# Proto_buttons.net
KiCad netlist of a schematic drawn in Altium Designer
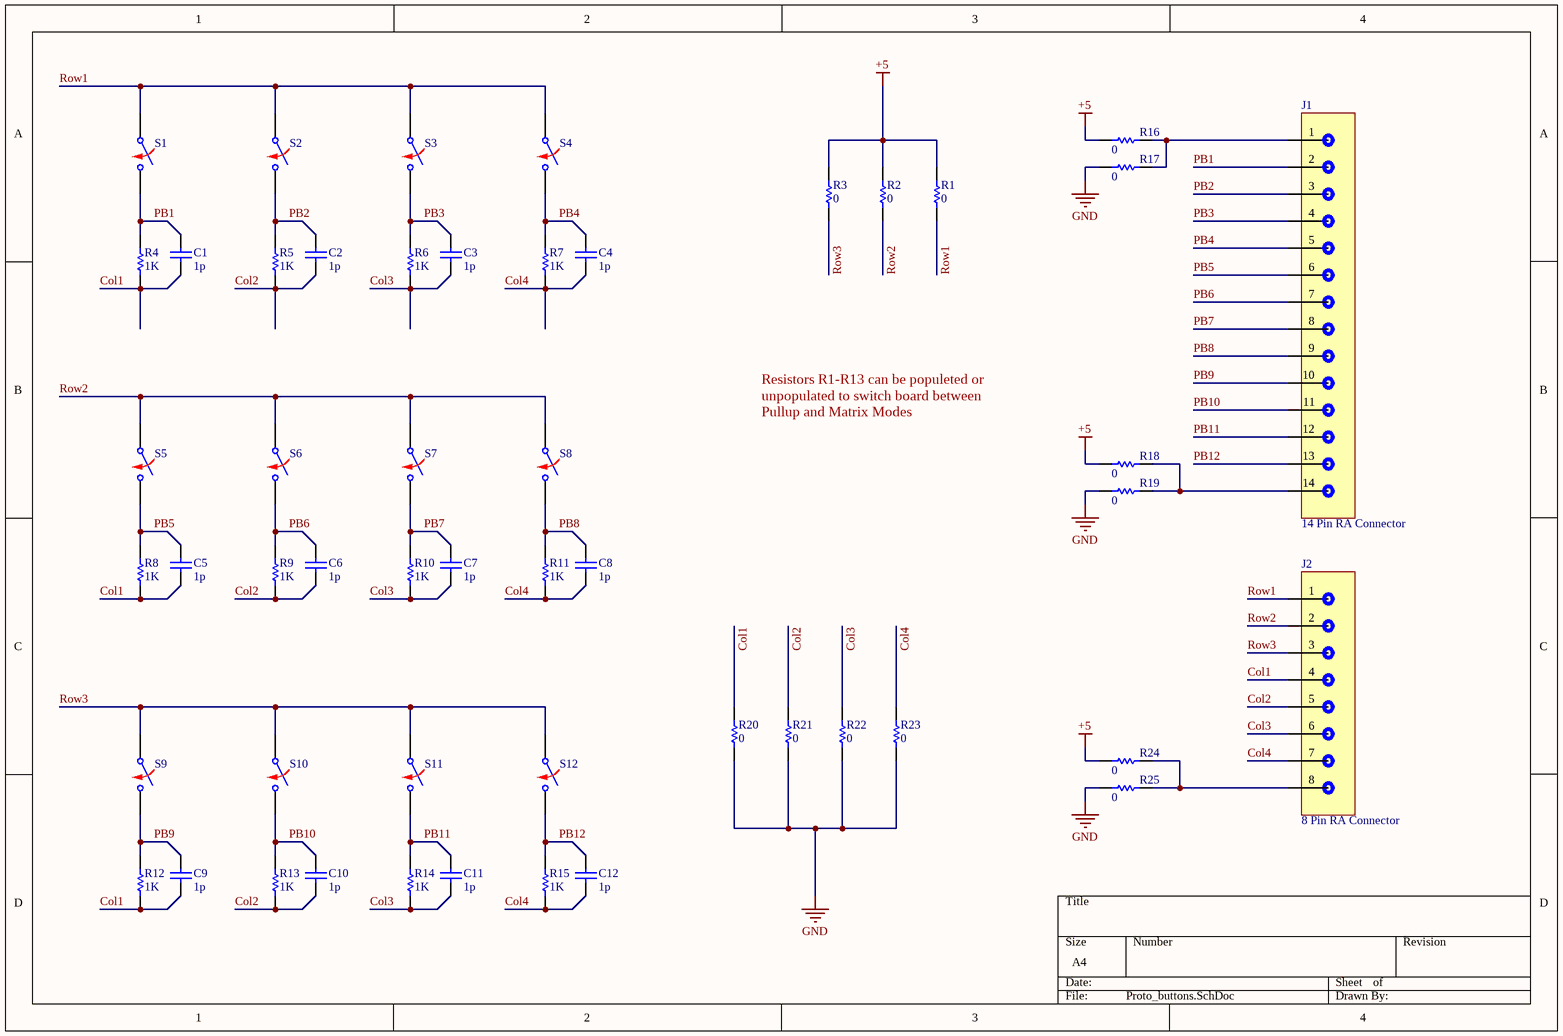
[diagram p0: Proto_buttons.SchDoc]

(export (version "E")
  (design (tool "Eeschema 10.0.6"))
  (components
    (comp (ref "C1")
      (value "1p")
      (footprint "TDK_CC0603_N")
      (description "Capacitor")
      (libsource (lib "Simulation Generic Components") (part "Capacitor"))
    )
    (comp (ref "C2")
      (value "1p")
      (footprint "TDK_CC0603_N")
      (description "Capacitor")
      (libsource (lib "Simulation Generic Components") (part "Capacitor"))
    )
    (comp (ref "C3")
      (value "1p")
      (footprint "TDK_CC0603_N")
      (description "Capacitor")
      (libsource (lib "Simulation Generic Components") (part "Capacitor"))
    )
    (comp (ref "C4")
      (value "1p")
      (footprint "TDK_CC0603_N")
      (description "Capacitor")
      (libsource (lib "Simulation Generic Components") (part "Capacitor"))
    )
    (comp (ref "C5")
      (value "1p")
      (footprint "TDK_CC0603_N")
      (description "Capacitor")
      (libsource (lib "Simulation Generic Components") (part "Capacitor"))
    )
    (comp (ref "C6")
      (value "1p")
      (footprint "TDK_CC0603_N")
      (description "Capacitor")
      (libsource (lib "Simulation Generic Components") (part "Capacitor"))
    )
    (comp (ref "C7")
      (value "1p")
      (footprint "TDK_CC0603_N")
      (description "Capacitor")
      (libsource (lib "Simulation Generic Components") (part "Capacitor"))
    )
    (comp (ref "C8")
      (value "1p")
      (footprint "TDK_CC0603_N")
      (description "Capacitor")
      (libsource (lib "Simulation Generic Components") (part "Capacitor"))
    )
    (comp (ref "C9")
      (value "1p")
      (footprint "TDK_CC0603_N")
      (description "Capacitor")
      (libsource (lib "Simulation Generic Components") (part "Capacitor"))
    )
    (comp (ref "C10")
      (value "1p")
      (footprint "TDK_CC0603_N")
      (description "Capacitor")
      (libsource (lib "Simulation Generic Components") (part "Capacitor"))
    )
    (comp (ref "C11")
      (value "1p")
      (footprint "TDK_CC0603_N")
      (description "Capacitor")
      (libsource (lib "Simulation Generic Components") (part "Capacitor"))
    )
    (comp (ref "C12")
      (value "1p")
      (footprint "TDK_CC0603_N")
      (description "Capacitor")
      (libsource (lib "Simulation Generic Components") (part "Capacitor"))
    )
    (comp (ref "J1")
      (value "14 Pin RA Connector")
      (footprint "14pin-Edge Connector")
      (libsource (lib "BW_Symbols") (part "14 Pin RA Connector"))
    )
    (comp (ref "J2")
      (value "8 Pin RA Connector")
      (footprint "8pin-Edge Connector")
      (libsource (lib "BW_Symbols") (part "8 Pin RA Connector"))
    )
    (comp (ref "R1")
      (value "0")
      (footprint "Yageo_0603")
      (description "Resistor")
      (libsource (lib "Simulation Generic Components") (part "Resistor"))
    )
    (comp (ref "R2")
      (value "0")
      (footprint "Yageo_0603")
      (description "Resistor")
      (libsource (lib "Simulation Generic Components") (part "Resistor"))
    )
    (comp (ref "R3")
      (value "0")
      (footprint "Yageo_0603")
      (description "Resistor")
      (libsource (lib "Simulation Generic Components") (part "Resistor"))
    )
    (comp (ref "R4")
      (value "1K")
      (footprint "Yageo_0603")
      (description "Resistor")
      (libsource (lib "Simulation Generic Components") (part "Resistor"))
    )
    (comp (ref "R5")
      (value "1K")
      (footprint "Yageo_0603")
      (description "Resistor")
      (libsource (lib "Simulation Generic Components") (part "Resistor"))
    )
    (comp (ref "R6")
      (value "1K")
      (footprint "Yageo_0603")
      (description "Resistor")
      (libsource (lib "Simulation Generic Components") (part "Resistor"))
    )
    (comp (ref "R7")
      (value "1K")
      (footprint "Yageo_0603")
      (description "Resistor")
      (libsource (lib "Simulation Generic Components") (part "Resistor"))
    )
    (comp (ref "R8")
      (value "1K")
      (footprint "Yageo_0603")
      (description "Resistor")
      (libsource (lib "Simulation Generic Components") (part "Resistor"))
    )
    (comp (ref "R9")
      (value "1K")
      (footprint "Yageo_0603")
      (description "Resistor")
      (libsource (lib "Simulation Generic Components") (part "Resistor"))
    )
    (comp (ref "R10")
      (value "1K")
      (footprint "Yageo_0603")
      (description "Resistor")
      (libsource (lib "Simulation Generic Components") (part "Resistor"))
    )
    (comp (ref "R11")
      (value "1K")
      (footprint "Yageo_0603")
      (description "Resistor")
      (libsource (lib "Simulation Generic Components") (part "Resistor"))
    )
    (comp (ref "R12")
      (value "1K")
      (footprint "Yageo_0603")
      (description "Resistor")
      (libsource (lib "Simulation Generic Components") (part "Resistor"))
    )
    (comp (ref "R13")
      (value "1K")
      (footprint "Yageo_0603")
      (description "Resistor")
      (libsource (lib "Simulation Generic Components") (part "Resistor"))
    )
    (comp (ref "R14")
      (value "1K")
      (footprint "Yageo_0603")
      (description "Resistor")
      (libsource (lib "Simulation Generic Components") (part "Resistor"))
    )
    (comp (ref "R15")
      (value "1K")
      (footprint "Yageo_0603")
      (description "Resistor")
      (libsource (lib "Simulation Generic Components") (part "Resistor"))
    )
    (comp (ref "R16")
      (value "0")
      (footprint "Yageo_0603")
      (description "Resistor")
      (libsource (lib "Simulation Generic Components") (part "Resistor"))
    )
    (comp (ref "R17")
      (value "0")
      (footprint "Yageo_0603")
      (description "Resistor")
      (libsource (lib "Simulation Generic Components") (part "Resistor"))
    )
    (comp (ref "R18")
      (value "0")
      (footprint "Yageo_0603")
      (description "Resistor")
      (libsource (lib "Simulation Generic Components") (part "Resistor"))
    )
    (comp (ref "R19")
      (value "0")
      (footprint "Yageo_0603")
      (description "Resistor")
      (libsource (lib "Simulation Generic Components") (part "Resistor"))
    )
    (comp (ref "R20")
      (value "0")
      (footprint "Yageo_0603")
      (description "Resistor")
      (libsource (lib "Simulation Generic Components") (part "Resistor"))
    )
    (comp (ref "R21")
      (value "0")
      (footprint "Yageo_0603")
      (description "Resistor")
      (libsource (lib "Simulation Generic Components") (part "Resistor"))
    )
    (comp (ref "R22")
      (value "0")
      (footprint "Yageo_0603")
      (description "Resistor")
      (libsource (lib "Simulation Generic Components") (part "Resistor"))
    )
    (comp (ref "R23")
      (value "0")
      (footprint "Yageo_0603")
      (description "Resistor")
      (libsource (lib "Simulation Generic Components") (part "Resistor"))
    )
    (comp (ref "R24")
      (value "0")
      (footprint "Yageo_0603")
      (description "Resistor")
      (libsource (lib "Simulation Generic Components") (part "Resistor"))
    )
    (comp (ref "R25")
      (value "0")
      (footprint "Yageo_0603")
      (description "Resistor")
      (libsource (lib "Simulation Generic Components") (part "Resistor"))
    )
    (comp (ref "S1")
      (value "Switch Normally Opened")
      (footprint "SW_SWT0310-043016GSA_REVA")
      (libsource (lib "Simulation Generic Components") (part "SW NO"))
    )
    (comp (ref "S2")
      (value "Switch Normally Opened")
      (footprint "SW_SWT0310-043016GSA_REVA")
      (libsource (lib "Simulation Generic Components") (part "SW NO"))
    )
    (comp (ref "S3")
      (value "Switch Normally Opened")
      (footprint "SW_SWT0310-043016GSA_REVA")
      (libsource (lib "Simulation Generic Components") (part "SW NO"))
    )
    (comp (ref "S4")
      (value "Switch Normally Opened")
      (footprint "SW_SWT0310-043016GSA_REVA")
      (libsource (lib "Simulation Generic Components") (part "SW NO"))
    )
    (comp (ref "S5")
      (value "Switch Normally Opened")
      (footprint "SW_SWT0310-043016GSA_REVA")
      (libsource (lib "Simulation Generic Components") (part "SW NO"))
    )
    (comp (ref "S6")
      (value "Switch Normally Opened")
      (footprint "SW_SWT0310-043016GSA_REVA")
      (libsource (lib "Simulation Generic Components") (part "SW NO"))
    )
    (comp (ref "S7")
      (value "Switch Normally Opened")
      (footprint "SW_SWT0310-043016GSA_REVA")
      (libsource (lib "Simulation Generic Components") (part "SW NO"))
    )
    (comp (ref "S8")
      (value "Switch Normally Opened")
      (footprint "SW_SWT0310-043016GSA_REVA")
      (libsource (lib "Simulation Generic Components") (part "SW NO"))
    )
    (comp (ref "S9")
      (value "Switch Normally Opened")
      (footprint "SW_SWT0310-043016GSA_REVA")
      (libsource (lib "Simulation Generic Components") (part "SW NO"))
    )
    (comp (ref "S10")
      (value "Switch Normally Opened")
      (footprint "SW_SWT0310-043016GSA_REVA")
      (libsource (lib "Simulation Generic Components") (part "SW NO"))
    )
    (comp (ref "S11")
      (value "Switch Normally Opened")
      (footprint "SW_SWT0310-043016GSA_REVA")
      (libsource (lib "Simulation Generic Components") (part "SW NO"))
    )
    (comp (ref "S12")
      (value "Switch Normally Opened")
      (footprint "SW_SWT0310-043016GSA_REVA")
      (libsource (lib "Simulation Generic Components") (part "SW NO"))
    )
  )
  (nets
    (net (code "1") (name "+5") (class "Default")
      (node (ref "R1") (pin "1") (pinfunction "1_1") (pintype "passive"))
      (node (ref "R16") (pin "2") (pinfunction "2_2") (pintype "passive"))
      (node (ref "R18") (pin "1") (pinfunction "1_1") (pintype "passive"))
      (node (ref "R2") (pin "1") (pinfunction "1_1") (pintype "passive"))
      (node (ref "R24") (pin "1") (pinfunction "1_1") (pintype "passive"))
      (node (ref "R3") (pin "1") (pinfunction "1_1") (pintype "passive"))
    )
    (net (code "2") (name "/Col1") (class "Default")
      (node (ref "C1") (pin "1") (pinfunction "1_1") (pintype "passive"))
      (node (ref "C5") (pin "1") (pinfunction "1_1") (pintype "passive"))
      (node (ref "C9") (pin "1") (pinfunction "1_1") (pintype "passive"))
      (node (ref "J2") (pin "4") (pinfunction "4_4") (pintype "passive"))
      (node (ref "R12") (pin "2") (pinfunction "2_2") (pintype "passive"))
      (node (ref "R20") (pin "1") (pinfunction "1_1") (pintype "passive"))
      (node (ref "R4") (pin "2") (pinfunction "2_2") (pintype "passive"))
      (node (ref "R8") (pin "2") (pinfunction "2_2") (pintype "passive"))
    )
    (net (code "3") (name "/Col2") (class "Default")
      (node (ref "C10") (pin "1") (pinfunction "1_1") (pintype "passive"))
      (node (ref "C2") (pin "1") (pinfunction "1_1") (pintype "passive"))
      (node (ref "C6") (pin "1") (pinfunction "1_1") (pintype "passive"))
      (node (ref "J2") (pin "5") (pinfunction "5_5") (pintype "passive"))
      (node (ref "R13") (pin "2") (pinfunction "2_2") (pintype "passive"))
      (node (ref "R21") (pin "1") (pinfunction "1_1") (pintype "passive"))
      (node (ref "R5") (pin "2") (pinfunction "2_2") (pintype "passive"))
      (node (ref "R9") (pin "2") (pinfunction "2_2") (pintype "passive"))
    )
    (net (code "4") (name "/Col3") (class "Default")
      (node (ref "C11") (pin "1") (pinfunction "1_1") (pintype "passive"))
      (node (ref "C3") (pin "1") (pinfunction "1_1") (pintype "passive"))
      (node (ref "C7") (pin "1") (pinfunction "1_1") (pintype "passive"))
      (node (ref "J2") (pin "6") (pinfunction "6_6") (pintype "passive"))
      (node (ref "R10") (pin "2") (pinfunction "2_2") (pintype "passive"))
      (node (ref "R14") (pin "2") (pinfunction "2_2") (pintype "passive"))
      (node (ref "R22") (pin "1") (pinfunction "1_1") (pintype "passive"))
      (node (ref "R6") (pin "2") (pinfunction "2_2") (pintype "passive"))
    )
    (net (code "5") (name "/Col4") (class "Default")
      (node (ref "C12") (pin "1") (pinfunction "1_1") (pintype "passive"))
      (node (ref "C4") (pin "1") (pinfunction "1_1") (pintype "passive"))
      (node (ref "C8") (pin "1") (pinfunction "1_1") (pintype "passive"))
      (node (ref "J2") (pin "7") (pinfunction "7_7") (pintype "passive"))
      (node (ref "R11") (pin "2") (pinfunction "2_2") (pintype "passive"))
      (node (ref "R15") (pin "2") (pinfunction "2_2") (pintype "passive"))
      (node (ref "R23") (pin "1") (pinfunction "1_1") (pintype "passive"))
      (node (ref "R7") (pin "2") (pinfunction "2_2") (pintype "passive"))
    )
    (net (code "6") (name "/PB1") (class "Default")
      (node (ref "C1") (pin "2") (pinfunction "2_2") (pintype "passive"))
      (node (ref "J1") (pin "2") (pinfunction "2_2") (pintype "passive"))
      (node (ref "R4") (pin "1") (pinfunction "1_1") (pintype "passive"))
      (node (ref "S1") (pin "2") (pinfunction "2_2") (pintype "passive"))
    )
    (net (code "7") (name "/PB2") (class "Default")
      (node (ref "C2") (pin "2") (pinfunction "2_2") (pintype "passive"))
      (node (ref "J1") (pin "3") (pinfunction "3_3") (pintype "passive"))
      (node (ref "R5") (pin "1") (pinfunction "1_1") (pintype "passive"))
      (node (ref "S2") (pin "2") (pinfunction "2_2") (pintype "passive"))
    )
    (net (code "8") (name "/PB3") (class "Default")
      (node (ref "C3") (pin "2") (pinfunction "2_2") (pintype "passive"))
      (node (ref "J1") (pin "4") (pinfunction "4_4") (pintype "passive"))
      (node (ref "R6") (pin "1") (pinfunction "1_1") (pintype "passive"))
      (node (ref "S3") (pin "2") (pinfunction "2_2") (pintype "passive"))
    )
    (net (code "9") (name "/PB4") (class "Default")
      (node (ref "C4") (pin "2") (pinfunction "2_2") (pintype "passive"))
      (node (ref "J1") (pin "5") (pinfunction "5_5") (pintype "passive"))
      (node (ref "R7") (pin "1") (pinfunction "1_1") (pintype "passive"))
      (node (ref "S4") (pin "2") (pinfunction "2_2") (pintype "passive"))
    )
    (net (code "10") (name "/PB5") (class "Default")
      (node (ref "C5") (pin "2") (pinfunction "2_2") (pintype "passive"))
      (node (ref "J1") (pin "6") (pinfunction "6_6") (pintype "passive"))
      (node (ref "R8") (pin "1") (pinfunction "1_1") (pintype "passive"))
      (node (ref "S5") (pin "2") (pinfunction "2_2") (pintype "passive"))
    )
    (net (code "11") (name "/PB6") (class "Default")
      (node (ref "C6") (pin "2") (pinfunction "2_2") (pintype "passive"))
      (node (ref "J1") (pin "7") (pinfunction "7_7") (pintype "passive"))
      (node (ref "R9") (pin "1") (pinfunction "1_1") (pintype "passive"))
      (node (ref "S6") (pin "2") (pinfunction "2_2") (pintype "passive"))
    )
    (net (code "12") (name "/PB7") (class "Default")
      (node (ref "C7") (pin "2") (pinfunction "2_2") (pintype "passive"))
      (node (ref "J1") (pin "8") (pinfunction "8_8") (pintype "passive"))
      (node (ref "R10") (pin "1") (pinfunction "1_1") (pintype "passive"))
      (node (ref "S7") (pin "2") (pinfunction "2_2") (pintype "passive"))
    )
    (net (code "13") (name "/PB8") (class "Default")
      (node (ref "C8") (pin "2") (pinfunction "2_2") (pintype "passive"))
      (node (ref "J1") (pin "9") (pinfunction "9_9") (pintype "passive"))
      (node (ref "R11") (pin "1") (pinfunction "1_1") (pintype "passive"))
      (node (ref "S8") (pin "2") (pinfunction "2_2") (pintype "passive"))
    )
    (net (code "14") (name "/PB9") (class "Default")
      (node (ref "C9") (pin "2") (pinfunction "2_2") (pintype "passive"))
      (node (ref "J1") (pin "10") (pinfunction "10_10") (pintype "passive"))
      (node (ref "R12") (pin "1") (pinfunction "1_1") (pintype "passive"))
      (node (ref "S9") (pin "2") (pinfunction "2_2") (pintype "passive"))
    )
    (net (code "15") (name "/PB10") (class "Default")
      (node (ref "C10") (pin "2") (pinfunction "2_2") (pintype "passive"))
      (node (ref "J1") (pin "11") (pinfunction "11_11") (pintype "passive"))
      (node (ref "R13") (pin "1") (pinfunction "1_1") (pintype "passive"))
      (node (ref "S10") (pin "2") (pinfunction "2_2") (pintype "passive"))
    )
    (net (code "16") (name "/PB11") (class "Default")
      (node (ref "C11") (pin "2") (pinfunction "2_2") (pintype "passive"))
      (node (ref "J1") (pin "12") (pinfunction "12_12") (pintype "passive"))
      (node (ref "R14") (pin "1") (pinfunction "1_1") (pintype "passive"))
      (node (ref "S11") (pin "2") (pinfunction "2_2") (pintype "passive"))
    )
    (net (code "17") (name "/PB12") (class "Default")
      (node (ref "C12") (pin "2") (pinfunction "2_2") (pintype "passive"))
      (node (ref "J1") (pin "13") (pinfunction "13_13") (pintype "passive"))
      (node (ref "R15") (pin "1") (pinfunction "1_1") (pintype "passive"))
      (node (ref "S12") (pin "2") (pinfunction "2_2") (pintype "passive"))
    )
    (net (code "18") (name "/Row1") (class "Default")
      (node (ref "J2") (pin "1") (pinfunction "1_1") (pintype "passive"))
      (node (ref "R1") (pin "2") (pinfunction "2_2") (pintype "passive"))
      (node (ref "S1") (pin "1") (pinfunction "1_1") (pintype "passive"))
      (node (ref "S2") (pin "1") (pinfunction "1_1") (pintype "passive"))
      (node (ref "S3") (pin "1") (pinfunction "1_1") (pintype "passive"))
      (node (ref "S4") (pin "1") (pinfunction "1_1") (pintype "passive"))
    )
    (net (code "19") (name "/Row2") (class "Default")
      (node (ref "J2") (pin "2") (pinfunction "2_2") (pintype "passive"))
      (node (ref "R2") (pin "2") (pinfunction "2_2") (pintype "passive"))
      (node (ref "S5") (pin "1") (pinfunction "1_1") (pintype "passive"))
      (node (ref "S6") (pin "1") (pinfunction "1_1") (pintype "passive"))
      (node (ref "S7") (pin "1") (pinfunction "1_1") (pintype "passive"))
      (node (ref "S8") (pin "1") (pinfunction "1_1") (pintype "passive"))
    )
    (net (code "20") (name "/Row3") (class "Default")
      (node (ref "J2") (pin "3") (pinfunction "3_3") (pintype "passive"))
      (node (ref "R3") (pin "2") (pinfunction "2_2") (pintype "passive"))
      (node (ref "S10") (pin "1") (pinfunction "1_1") (pintype "passive"))
      (node (ref "S11") (pin "1") (pinfunction "1_1") (pintype "passive"))
      (node (ref "S12") (pin "1") (pinfunction "1_1") (pintype "passive"))
      (node (ref "S9") (pin "1") (pinfunction "1_1") (pintype "passive"))
    )
    (net (code "21") (name "GND") (class "Default")
      (node (ref "R17") (pin "1") (pinfunction "1_1") (pintype "passive"))
      (node (ref "R19") (pin "1") (pinfunction "1_1") (pintype "passive"))
      (node (ref "R20") (pin "2") (pinfunction "2_2") (pintype "passive"))
      (node (ref "R21") (pin "2") (pinfunction "2_2") (pintype "passive"))
      (node (ref "R22") (pin "2") (pinfunction "2_2") (pintype "passive"))
      (node (ref "R23") (pin "2") (pinfunction "2_2") (pintype "passive"))
      (node (ref "R25") (pin "1") (pinfunction "1_1") (pintype "passive"))
    )
    (net (code "22") (name "Net-(J1-Pad1)") (class "Default")
      (node (ref "J1") (pin "1") (pinfunction "1_1") (pintype "passive"))
      (node (ref "R16") (pin "1") (pinfunction "1_1") (pintype "passive"))
      (node (ref "R17") (pin "2") (pinfunction "2_2") (pintype "passive"))
    )
    (net (code "23") (name "Net-(J1-Pad14)") (class "Default")
      (node (ref "J1") (pin "14") (pinfunction "14_14") (pintype "passive"))
      (node (ref "R18") (pin "2") (pinfunction "2_2") (pintype "passive"))
      (node (ref "R19") (pin "2") (pinfunction "2_2") (pintype "passive"))
    )
    (net (code "24") (name "Net-(J2-Pad8)") (class "Default")
      (node (ref "J2") (pin "8") (pinfunction "8_8") (pintype "passive"))
      (node (ref "R24") (pin "2") (pinfunction "2_2") (pintype "passive"))
      (node (ref "R25") (pin "2") (pinfunction "2_2") (pintype "passive"))
    )
  )
)
